# PIC_BSL.net
KiCad netlist of a schematic drawn in Altium Designer
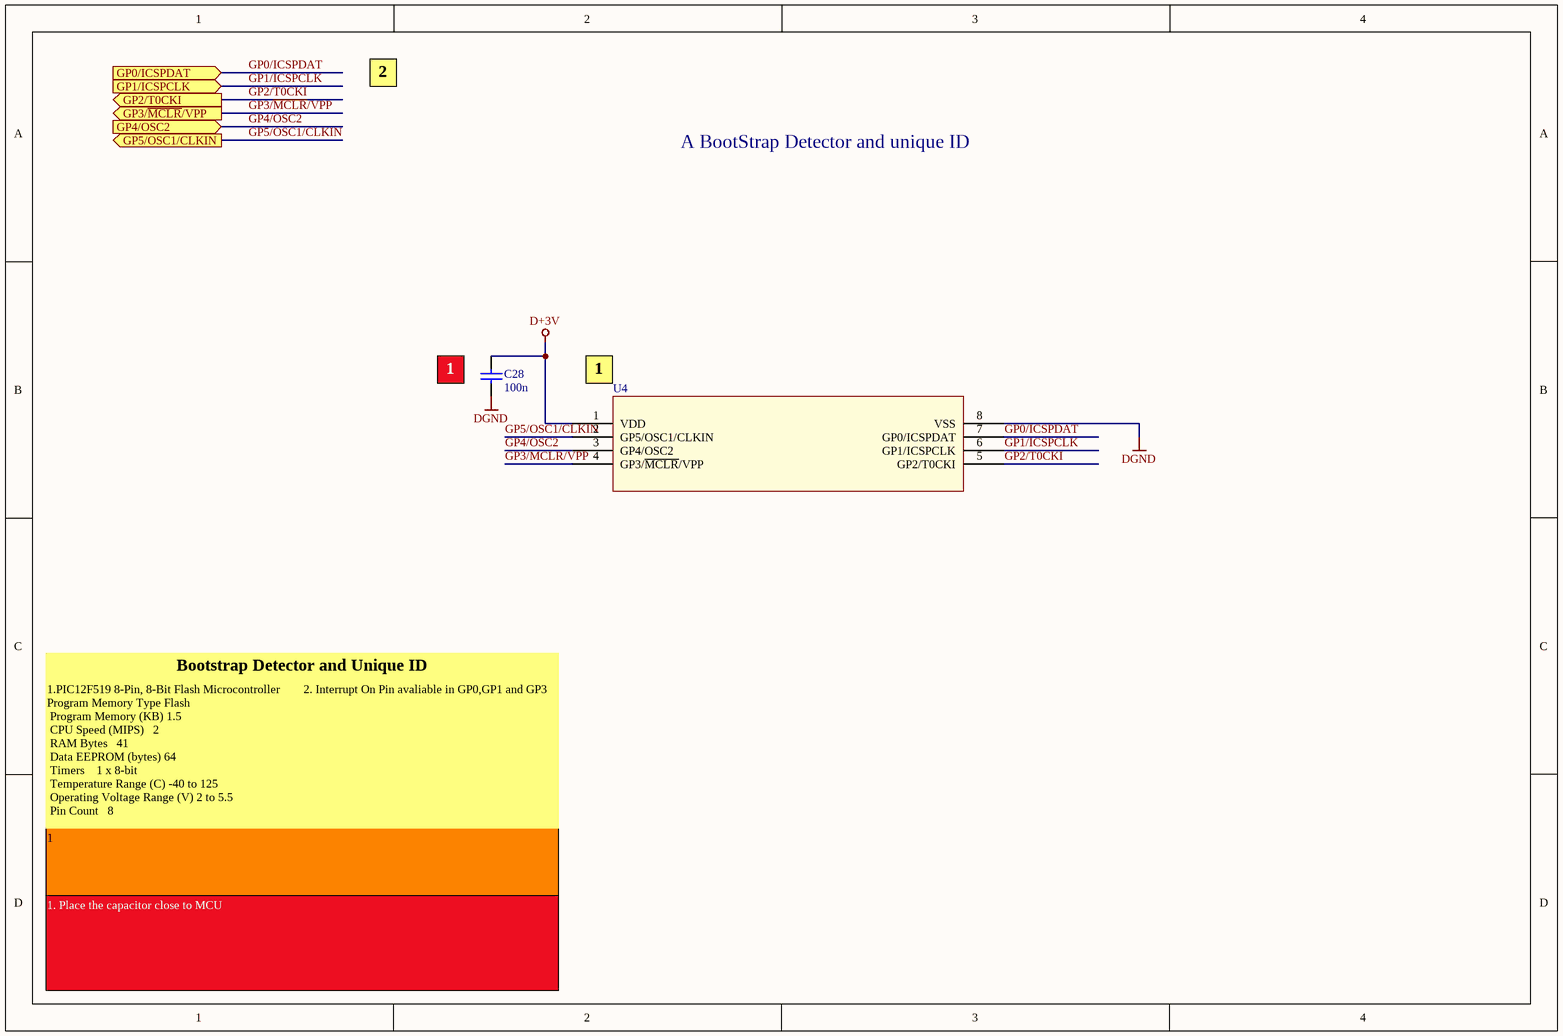
[diagram p0: PIC_BSL.SchDoc]

(export (version "E")
  (design (tool "Eeschema 10.0.6"))
  (components
    (comp (ref "C28")
      (value "100n")
      (footprint "CC1005-0402")
      (description "Capacitor (Semiconductor SIM Model)")
      (fields (field (name "Comment") "Cap Semi"))
      (libsource (lib "Z1_Project") (part "Cap Semi"))
    )
    (comp (ref "U4")
      (value "8-Bit CMOS Microcontroller")
      (footprint "DFN 2x3x0.9mm")
      (libsource (lib "Z1_Project") (part "PIC12F589"))
    )
  )
  (nets
    (net (code "1") (name "/GP0{slash}ICSPDAT") (class "Default")
      (node (ref "U4") (pin "7") (pinfunction "GP0/ICSPDAT_7") (pintype "passive"))
    )
    (net (code "2") (name "/GP1{slash}ICSPCLK") (class "Default")
      (node (ref "U4") (pin "6") (pinfunction "GP1/ICSPCLK_6") (pintype "passive"))
    )
    (net (code "3") (name "/GP2{slash}T0CKI") (class "Default")
      (node (ref "U4") (pin "5") (pinfunction "GP2/T0CKI_5") (pintype "passive"))
    )
    (net (code "4") (name "/GP3{slash}~{MCLR}{slash}VPP") (class "Default")
      (node (ref "U4") (pin "4") (pinfunction "GP3/~{MCLR}/VPP_4") (pintype "passive"))
    )
    (net (code "5") (name "/GP4{slash}OSC2") (class "Default")
      (node (ref "U4") (pin "3") (pinfunction "GP4/OSC2_3") (pintype "passive"))
    )
    (net (code "6") (name "/GP5{slash}OSC1{slash}CLKIN") (class "Default")
      (node (ref "U4") (pin "2") (pinfunction "GP5/OSC1/CLKIN_2") (pintype "passive"))
    )
    (net (code "7") (name "D+3V") (class "Default")
      (node (ref "C28") (pin "2") (pinfunction "2_2") (pintype "passive"))
      (node (ref "U4") (pin "1") (pinfunction "VDD_1") (pintype "passive"))
    )
    (net (code "8") (name "DGND") (class "Default")
      (node (ref "C28") (pin "1") (pinfunction "1_1") (pintype "passive"))
      (node (ref "U4") (pin "8") (pinfunction "VSS_8") (pintype "passive"))
    )
  )
)
